# Battery_Management.net
KiCad netlist of a schematic drawn in Altium Designer
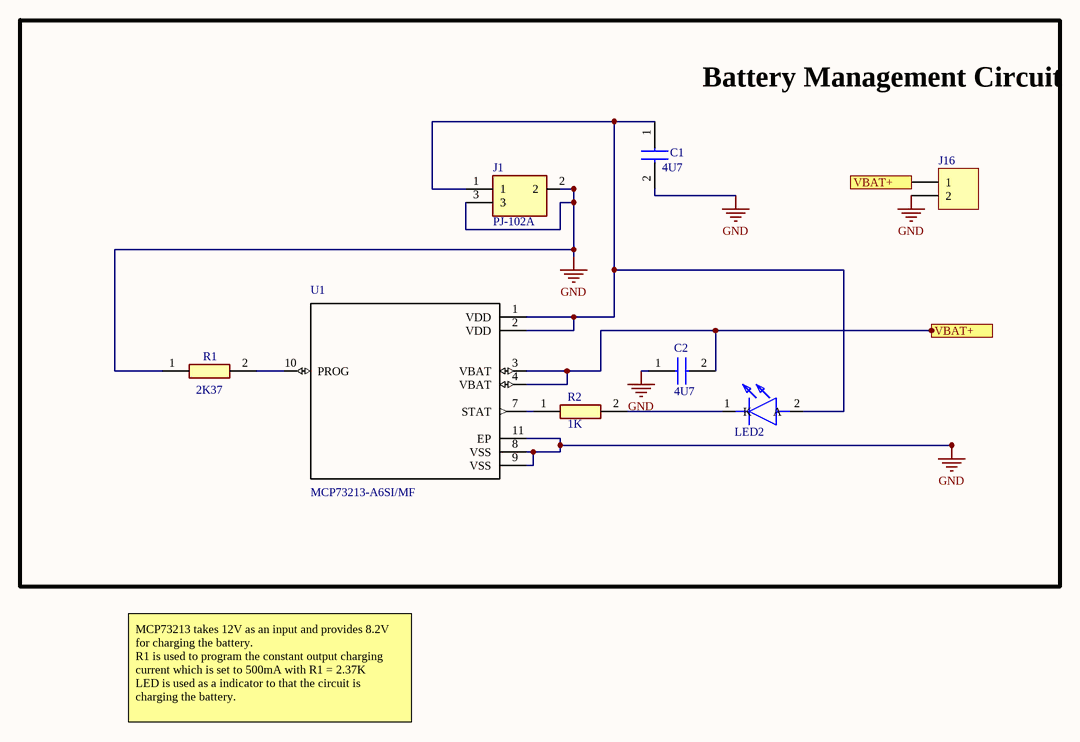
[diagram p0: Battery_Management.SchDoc]

(export (version "E")
  (design (tool "Eeschema 10.0.6"))
  (components
    (comp (ref "C1")
      (value "4U7")
      (footprint "SamacSys:CAPC1608X90N")
      (description "Capacitor")
      (fields
        (field (name "MANUFACTURER_PART_NUMBER") "GRM188R61E475KE11D")
        (field (name "MOUSER PART NUMBER") "81-GRM188R61E475KE1D")
      )
      (libsource (lib "*") (part "GRM188R61E475KE11D"))
    )
    (comp (ref "C2")
      (value "4U7")
      (footprint "SamacSys:CAPC1608X90N")
      (description "Capacitor")
      (fields
        (field (name "MANUFACTURER_PART_NUMBER") "GRM188R61E475KE11D")
        (field (name "MOUSER PART NUMBER") "81-GRM188R61E475KE1D")
      )
      (libsource (lib "*") (part "GRM188R61E475KE11D"))
    )
    (comp (ref "J1")
      (value "PJ-102A")
      (footprint "SamacSys:PJ-102AH")
      (description "Connector")
      (fields (field (name "MOUSER PART NUMBER") "490-PJ-102A"))
      (libsource (lib "*") (part "PJ-102A"))
    )
    (comp (ref "J16")
      (value "Header 2")
      (footprint "HDR1X2")
      (description "Header, 2-Pin")
      (fields
        (field (name "MANUFACTURER_PART_NUMBER") "BG301-04-A-0540-L-B")
        (field (name "DIGI-KEY PART NUMBER") "2073-BG301-02-A-0540-L-BCT-ND")
      )
      (libsource (lib "Miscellaneous Connectors") (part "Header 2"))
    )
    (comp (ref "LED2")
      (value "SML-D12U1WT86")
      (footprint "SamacSys:LEDC1608X65N")
      (description "LED")
      (fields
        (field (name "MOUSER PART NUMBER") "755-SML-D12U1WT86")
        (field (name "RS PART NUMBER") "1332870P")
      )
      (libsource (lib "*") (part "SML-D12U1WT86"))
    )
    (comp (ref "R1")
      (value "2K37")
      (footprint "SamacSys:RESC1608X55N")
      (description "Resistor")
      (fields
        (field (name "MANUFACTURER_PART_NUMBER") "ERJ-3EKF2371V")
        (field (name "MOUSER PART NUMBER") "667-ERJ-3EKF2371V")
      )
      (libsource (lib "*") (part "ERJ-3EKF2371V"))
    )
    (comp (ref "R2")
      (value "1K")
      (footprint "SamacSys:RESC1608X55N")
      (description "Resistor")
      (fields
        (field (name "MANUFACTURER_PART_NUMBER") "RC0603FR-071KL")
        (field (name "MOUSER PART NUMBER") "603-RC0603FR-071KL")
      )
      (libsource (lib "*") (part "RC0603FR-071KL"))
    )
    (comp (ref "U1")
      (value "MCP73213-A6SI/MF")
      (footprint "*SON50P300X300X100-11N")
      (description "MCP Series 16V Dual-Cell Li-Ion/Li-Polymer Battery Charge Management Controller")
      (fields (field (name "DIGI-KEY PART NUMBER") "MCP73213T-A6SI/MF"))
      (libsource (lib "MCP73213-A6SI_MF") (part "MCP73213-A6SI/MF"))
    )
  )
  (nets
    (net (code "1") (name "/VBAT+") (class "Default")
      (node (ref "C2") (pin "2") (pinfunction "2_2") (pintype "passive"))
      (node (ref "J16") (pin "1") (pinfunction "1_1") (pintype "passive"))
      (node (ref "U1") (pin "3") (pinfunction "VBAT_3") (pintype "bidirectional"))
      (node (ref "U1") (pin "4") (pinfunction "VBAT_4") (pintype "bidirectional"))
    )
    (net (code "2") (name "GND") (class "Default")
      (node (ref "C1") (pin "2") (pinfunction "2_2") (pintype "passive"))
      (node (ref "C2") (pin "1") (pinfunction "1_1") (pintype "passive"))
      (node (ref "J1") (pin "2") (pinfunction "2_2") (pintype "passive"))
      (node (ref "J1") (pin "3") (pinfunction "3_3") (pintype "passive"))
      (node (ref "J16") (pin "2") (pinfunction "2_2") (pintype "passive"))
      (node (ref "R1") (pin "1") (pinfunction "1_1") (pintype "passive"))
      (node (ref "U1") (pin "11") (pinfunction "EP_11") (pintype "power_in"))
      (node (ref "U1") (pin "8") (pinfunction "VSS_8") (pintype "power_in"))
      (node (ref "U1") (pin "9") (pinfunction "VSS_9") (pintype "power_in"))
    )
    (net (code "3") (name "Net-(LED2-A)") (class "Default")
      (node (ref "C1") (pin "1") (pinfunction "1_1") (pintype "passive"))
      (node (ref "J1") (pin "1") (pinfunction "1_1") (pintype "passive"))
      (node (ref "LED2") (pin "2") (pinfunction "A_2") (pintype "passive"))
      (node (ref "U1") (pin "1") (pinfunction "VDD_1") (pintype "power_in"))
      (node (ref "U1") (pin "2") (pinfunction "VDD_2") (pintype "power_in"))
    )
    (net (code "4") (name "Net-(LED2-K)") (class "Default")
      (node (ref "LED2") (pin "1") (pinfunction "K_1") (pintype "passive"))
      (node (ref "R2") (pin "2") (pinfunction "2_2") (pintype "passive"))
    )
    (net (code "5") (name "Net-(U1-PROG)") (class "Default")
      (node (ref "R1") (pin "2") (pinfunction "2_2") (pintype "passive"))
      (node (ref "U1") (pin "10") (pinfunction "PROG_10") (pintype "bidirectional"))
    )
    (net (code "6") (name "Net-(U1-STAT)") (class "Default")
      (node (ref "R2") (pin "1") (pinfunction "1_1") (pintype "passive"))
      (node (ref "U1") (pin "7") (pinfunction "STAT_7") (pintype "output"))
    )
  )
)
